# LDO.net
KiCad netlist of a schematic drawn in Altium Designer
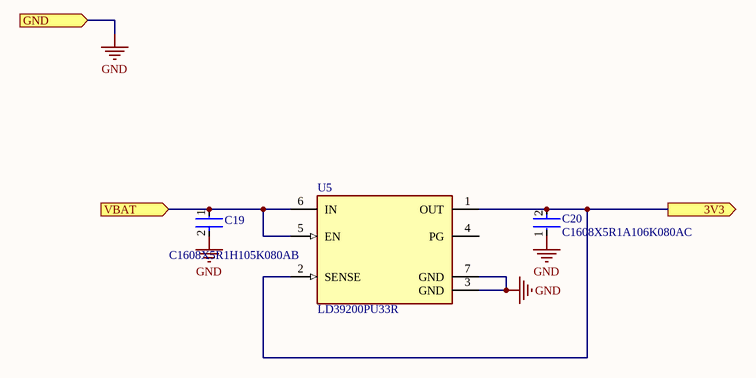
[diagram p0: LDO.SchDoc]

(export (version "E")
  (design (tool "Eeschema 10.0.6"))
  (components
    (comp (ref "C19")
      (value "C1608X5R1H105K080AB")
      (footprint "FP-C1608-080-0_1-IPC_B")
      (description "Multilayer Ceramic Capacitors 1μF ±10% 50V X5R SMD 0603")
      (fields (field (name "VOLTAGE") "50V") (field (name "TOLERANCE") "10%"))
      (libsource (lib "Altium Content Vault") (part "236180d848d6139a670b325ea6854c9"))
    )
    (comp (ref "C20")
      (value "C1608X5R1A106K080AC")
      (footprint "FP-C1608-080-0_1-MFG")
      (description "Multilayer Ceramic Capacitors 10μF ±10% 10V X5R SMD 0603")
      (fields (field (name "VOLTAGE") "10V") (field (name "TOLERANCE") "10%"))
      (libsource (lib "Altium Content Vault") (part "236180d848d6139a670b325ea6854c9"))
    )
    (comp (ref "U5")
      (value "LD39200PU33R")
      (footprint "FP-DFN6-7946637-MFG")
      (description "IC REG LINEAR 3.3V 2A 6DFN")
      (libsource (lib "Altium Content Vault") (part "f0cfe00d12cb984572f50007c934a2d"))
    )
  )
  (nets
    (net (code "1") (name "/3V3") (class "Default")
      (node (ref "C20") (pin "2") (pinfunction "2_2") (pintype "passive"))
      (node (ref "U5") (pin "1") (pinfunction "OUT_1") (pintype "power_in"))
      (node (ref "U5") (pin "2") (pinfunction "SENSE_2") (pintype "input"))
    )
    (net (code "2") (name "/VBAT") (class "Default")
      (node (ref "C19") (pin "1") (pinfunction "1_1") (pintype "passive"))
      (node (ref "U5") (pin "5") (pinfunction "EN_5") (pintype "input"))
      (node (ref "U5") (pin "6") (pinfunction "IN_6") (pintype "power_in"))
    )
    (net (code "3") (name "GND") (class "Default")
      (node (ref "C19") (pin "2") (pinfunction "2_2") (pintype "passive"))
      (node (ref "C20") (pin "1") (pinfunction "1_1") (pintype "passive"))
      (node (ref "U5") (pin "3") (pinfunction "GND_3") (pintype "power_in"))
      (node (ref "U5") (pin "7") (pinfunction "GND_7") (pintype "power_in"))
    )
    (net (code "4") (name "unconnected-(U5-PG-Pad4)") (class "Default")
      (node (ref "U5") (pin "4") (pinfunction "PG_4") (pintype "open_collector"))
    )
  )
)
